# twilight3.net
KiCad netlist of a schematic drawn in EAGLE
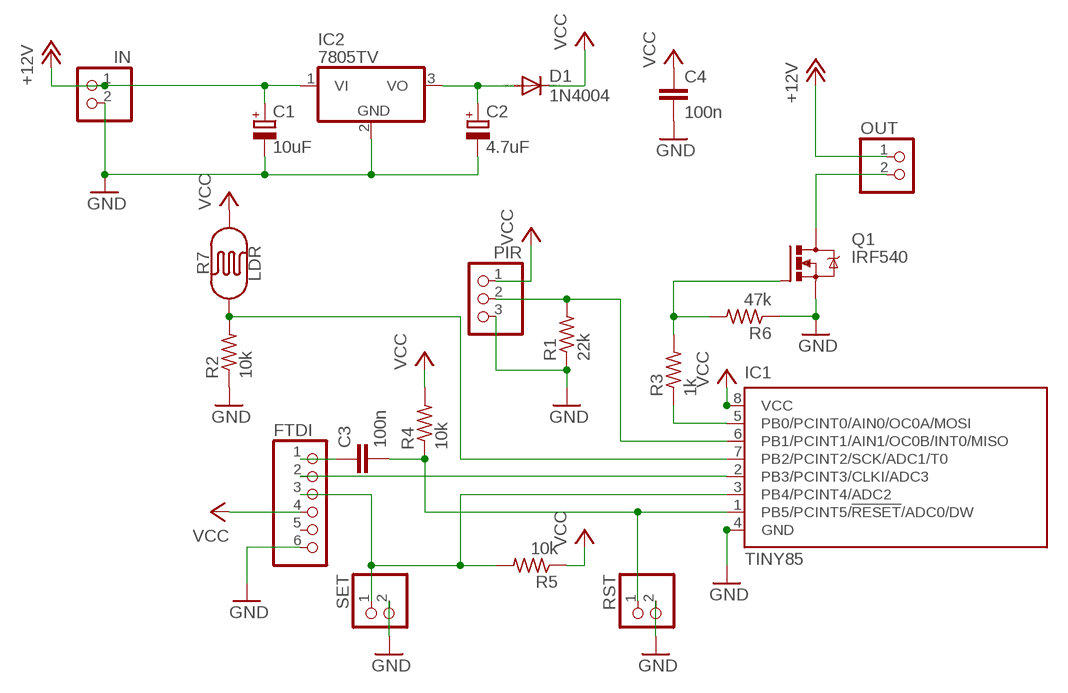
[diagram p0: schematic, sheet 1]

(export (version "E")
  (design (tool "Eeschema 10.0.6"))
  (components
    (comp (ref "C1")
      (value "10uF")
      (footprint "eagle-import:E2-5")
      (libsource (lib "eagle-import") (part "CPOL-EUE2-5"))
    )
    (comp (ref "C2")
      (value "4.7uF")
      (footprint "eagle-import:E2-5")
      (libsource (lib "eagle-import") (part "CPOL-EUE2-5"))
    )
    (comp (ref "C3")
      (value "100n")
      (footprint "eagle-import:C050-024X044")
      (libsource (lib "eagle-import") (part "C-EU050-024X044"))
    )
    (comp (ref "C4")
      (value "100n")
      (footprint "eagle-import:C050-024X044")
      (libsource (lib "eagle-import") (part "C-EU050-024X044"))
    )
    (comp (ref "D1")
      (value "1N4004")
      (footprint "eagle-import:DO41-10")
      (libsource (lib "eagle-import") (part "1N4004"))
    )
    (comp (ref "FTDI")
      (value "PINHD-1X6")
      (footprint "eagle-import:1X06")
      (libsource (lib "eagle-import") (part "PINHD-1X6"))
    )
    (comp (ref "IC1")
      (value "TINY85")
      (footprint "eagle-import:DIL08")
      (fields (field (name "MPN") "ATTINY13-20PU"))
      (libsource (lib "eagle-import") (part "TINY13PU-20"))
    )
    (comp (ref "IC2")
      (value "7805TV")
      (footprint "eagle-import:TO220V")
      (libsource (lib "eagle-import") (part "78TV05"))
    )
    (comp (ref "IN")
      (value "PINHD-1X2")
      (footprint "eagle-import:1X02")
      (libsource (lib "eagle-import") (part "PINHD-1X2"))
    )
    (comp (ref "OUT")
      (value "PINHD-1X2")
      (footprint "eagle-import:1X02")
      (libsource (lib "eagle-import") (part "PINHD-1X2"))
    )
    (comp (ref "PIR")
      (value "PINHD-1X3")
      (footprint "eagle-import:1X03")
      (libsource (lib "eagle-import") (part "PINHD-1X3"))
    )
    (comp (ref "Q1")
      (value "IRF540")
      (footprint "eagle-import:TO220BV")
      (libsource (lib "eagle-import") (part "IRF540"))
    )
    (comp (ref "R1")
      (value "22k")
      (footprint "eagle-import:0207_2V")
      (libsource (lib "eagle-import") (part "R-US_0207/2V"))
    )
    (comp (ref "R2")
      (value "10k")
      (footprint "eagle-import:0207_2V")
      (libsource (lib "eagle-import") (part "R-US_0207/2V"))
    )
    (comp (ref "R3")
      (value "1k")
      (footprint "eagle-import:0207_10")
      (libsource (lib "eagle-import") (part "R-US_0207/10"))
    )
    (comp (ref "R4")
      (value "10k")
      (footprint "eagle-import:0207_2V")
      (libsource (lib "eagle-import") (part "R-US_0207/2V"))
    )
    (comp (ref "R5")
      (value "10k")
      (footprint "eagle-import:0207_2V")
      (libsource (lib "eagle-import") (part "R-US_0207/2V"))
    )
    (comp (ref "R6")
      (value "47k")
      (footprint "eagle-import:0207_10")
      (libsource (lib "eagle-import") (part "R-US_0207/10"))
    )
    (comp (ref "R7")
      (value "LDR")
      (footprint "eagle-import:PHOTOCELL")
      (libsource (lib "eagle-import") (part "PHOTOCELLPTH"))
    )
    (comp (ref "RST")
      (value "PINHD-1X2")
      (footprint "eagle-import:1X02")
      (libsource (lib "eagle-import") (part "PINHD-1X2"))
    )
    (comp (ref "SET")
      (value "PINHD-1X2")
      (footprint "eagle-import:1X02")
      (libsource (lib "eagle-import") (part "PINHD-1X2"))
    )
  )
  (nets
    (net (code "1") (name "+12V") (class "Default")
      (node (ref "C1") (pin "+") (pinfunction "+_+") (pintype "passive"))
      (node (ref "IC2") (pin "1") (pinfunction "VI_1") (pintype "input"))
      (node (ref "IN") (pin "1") (pinfunction "1_1") (pintype "passive"))
      (node (ref "OUT") (pin "1") (pinfunction "1_1") (pintype "passive"))
    )
    (net (code "2") (name "GND") (class "Default")
      (node (ref "C1") (pin "-") (pinfunction "-_-") (pintype "passive"))
      (node (ref "C2") (pin "-") (pinfunction "-_-") (pintype "passive"))
      (node (ref "C4") (pin "2") (pinfunction "2_2") (pintype "passive"))
      (node (ref "FTDI") (pin "6") (pinfunction "6_6") (pintype "passive"))
      (node (ref "IC1") (pin "4") (pinfunction "GND_4") (pintype "power_in"))
      (node (ref "IC2") (pin "2") (pinfunction "GND_2") (pintype "passive"))
      (node (ref "IN") (pin "2") (pinfunction "2_2") (pintype "passive"))
      (node (ref "PIR") (pin "3") (pinfunction "3_3") (pintype "passive"))
      (node (ref "Q1") (pin "S") (pinfunction "S_S") (pintype "passive"))
      (node (ref "R1") (pin "1") (pinfunction "1_1") (pintype "passive"))
      (node (ref "R2") (pin "1") (pinfunction "1_1") (pintype "passive"))
      (node (ref "R6") (pin "1") (pinfunction "1_1") (pintype "passive"))
      (node (ref "RST") (pin "2") (pinfunction "2_2") (pintype "passive"))
      (node (ref "SET") (pin "2") (pinfunction "2_2") (pintype "passive"))
    )
    (net (code "3") (name "Net-(C3-Pad1)") (class "Default")
      (node (ref "C3") (pin "1") (pinfunction "1_1") (pintype "passive"))
      (node (ref "FTDI") (pin "1") (pinfunction "1_1") (pintype "passive"))
    )
    (net (code "4") (name "Net-(IC1-PB0{slash}PCINT0{slash}AIN0{slash}OC0A{slash}MOSI)") (class "Default")
      (node (ref "IC1") (pin "5") (pinfunction "PB0/PCINT0/AIN0/OC0A/MOSI_5") (pintype "bidirectional"))
      (node (ref "R3") (pin "1") (pinfunction "1_1") (pintype "passive"))
    )
    (net (code "5") (name "Net-(IC1-PB1{slash}PCINT1{slash}AIN1{slash}OC0B{slash}INT0{slash}MISO)") (class "Default")
      (node (ref "IC1") (pin "6") (pinfunction "PB1/PCINT1/AIN1/OC0B/INT0/MISO_6") (pintype "bidirectional"))
      (node (ref "PIR") (pin "2") (pinfunction "2_2") (pintype "passive"))
      (node (ref "R1") (pin "2") (pinfunction "2_2") (pintype "passive"))
    )
    (net (code "6") (name "Net-(IC1-PB2{slash}PCINT2{slash}SCK{slash}ADC1{slash}T0)") (class "Default")
      (node (ref "IC1") (pin "7") (pinfunction "PB2/PCINT2/SCK/ADC1/T0_7") (pintype "bidirectional"))
      (node (ref "R2") (pin "2") (pinfunction "2_2") (pintype "passive"))
      (node (ref "R7") (pin "1") (pinfunction "P$1_1") (pintype "bidirectional"))
    )
    (net (code "7") (name "Net-(IC1-PB3{slash}PCINT3{slash}CLKI{slash}ADC3)") (class "Default")
      (node (ref "FTDI") (pin "2") (pinfunction "2_2") (pintype "passive"))
      (node (ref "IC1") (pin "2") (pinfunction "PB3/PCINT3/CLKI/ADC3_2") (pintype "bidirectional"))
    )
    (net (code "8") (name "Net-(IC1-PB4{slash}PCINT4{slash}ADC2)") (class "Default")
      (node (ref "FTDI") (pin "3") (pinfunction "3_3") (pintype "passive"))
      (node (ref "IC1") (pin "3") (pinfunction "PB4/PCINT4/ADC2_3") (pintype "bidirectional"))
      (node (ref "R5") (pin "2") (pinfunction "2_2") (pintype "passive"))
      (node (ref "SET") (pin "1") (pinfunction "1_1") (pintype "passive"))
    )
    (net (code "9") (name "Net-(IC1-PB5{slash}PCINT5{slash}~{RESET}{slash}ADC0{slash}DW)") (class "Default")
      (node (ref "C3") (pin "2") (pinfunction "2_2") (pintype "passive"))
      (node (ref "IC1") (pin "1") (pinfunction "PB5/PCINT5/~{RESET}/ADC0/DW_1") (pintype "bidirectional"))
      (node (ref "R4") (pin "1") (pinfunction "1_1") (pintype "passive"))
      (node (ref "RST") (pin "1") (pinfunction "1_1") (pintype "passive"))
    )
    (net (code "10") (name "Net-(IC2-VO)") (class "Default")
      (node (ref "C2") (pin "+") (pinfunction "+_+") (pintype "passive"))
      (node (ref "D1") (pin "A") (pinfunction "A_A") (pintype "passive"))
      (node (ref "IC2") (pin "3") (pinfunction "VO_3") (pintype "passive"))
    )
    (net (code "11") (name "Net-(OUT-Pad2)") (class "Default")
      (node (ref "OUT") (pin "2") (pinfunction "2_2") (pintype "passive"))
      (node (ref "Q1") (pin "D") (pinfunction "D_D") (pintype "passive"))
    )
    (net (code "12") (name "Net-(Q1-PadG)") (class "Default")
      (node (ref "Q1") (pin "G") (pinfunction "G_G") (pintype "passive"))
      (node (ref "R3") (pin "2") (pinfunction "2_2") (pintype "passive"))
      (node (ref "R6") (pin "2") (pinfunction "2_2") (pintype "passive"))
    )
    (net (code "13") (name "VCC") (class "Default")
      (node (ref "C4") (pin "1") (pinfunction "1_1") (pintype "passive"))
      (node (ref "D1") (pin "C") (pinfunction "C_C") (pintype "passive"))
      (node (ref "FTDI") (pin "4") (pinfunction "4_4") (pintype "passive"))
      (node (ref "IC1") (pin "8") (pinfunction "VCC_8") (pintype "power_in"))
      (node (ref "PIR") (pin "1") (pinfunction "1_1") (pintype "passive"))
      (node (ref "R4") (pin "2") (pinfunction "2_2") (pintype "passive"))
      (node (ref "R5") (pin "1") (pinfunction "1_1") (pintype "passive"))
      (node (ref "R7") (pin "2") (pinfunction "P$2_2") (pintype "bidirectional"))
    )
    (net (code "14") (name "unconnected-(FTDI-Pad5)") (class "Default")
      (node (ref "FTDI") (pin "5") (pinfunction "5_5") (pintype "passive"))
    )
  )
)
